# cube.net
KiCad netlist of a schematic drawn in EAGLE
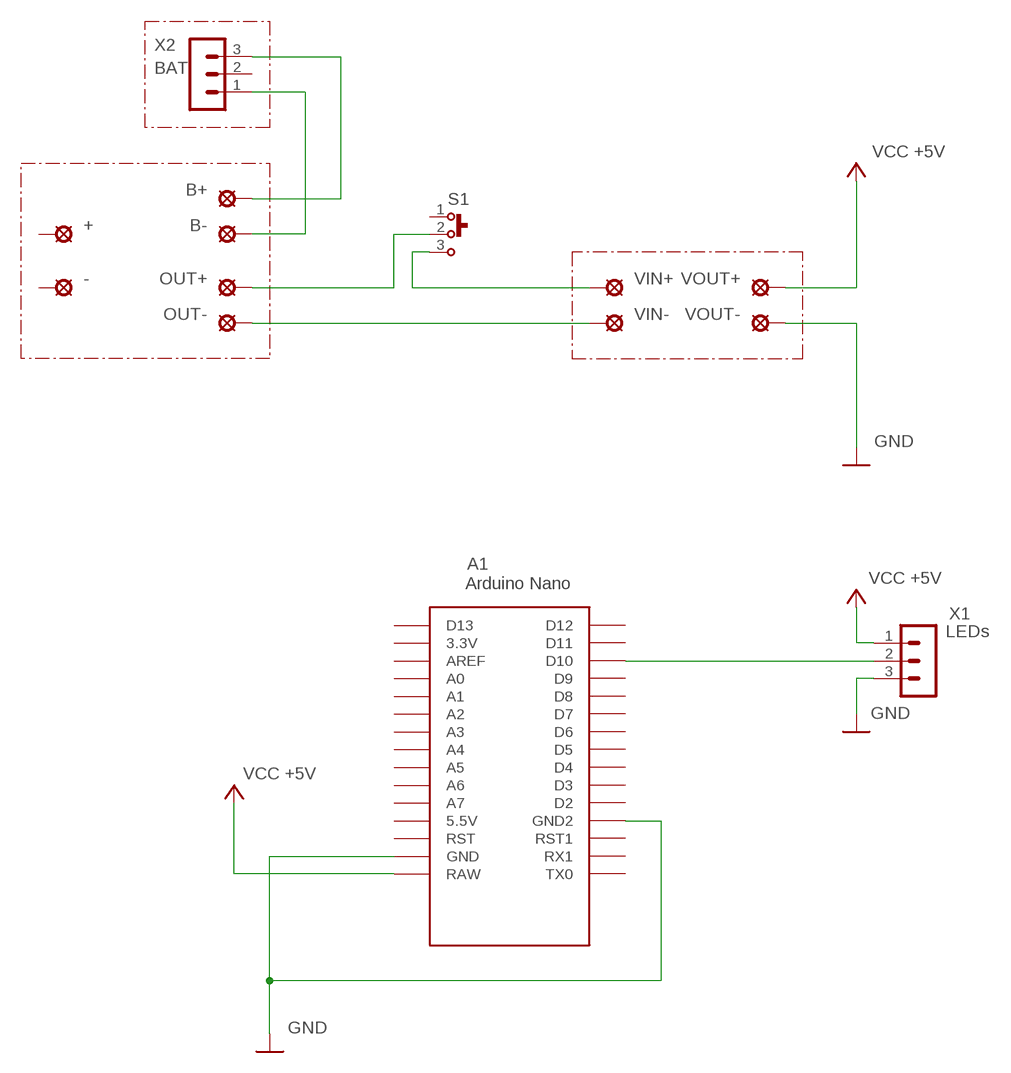
[diagram p0: schematic, sheet 1]

(export (version "E")
  (design (tool "Eeschema 10.0.6"))
  (components
    (comp (ref "+")
      (value "MCS08")
      (footprint "eagle-import:MCS08")
      (libsource (lib "eagle-import") (part "MCS08"))
    )
    (comp (ref "-")
      (value "MCS08")
      (footprint "eagle-import:MCS08")
      (libsource (lib "eagle-import") (part "MCS08"))
    )
    (comp (ref "A1")
      (value "NANO")
      (footprint "eagle-import:NANO")
      (libsource (lib "eagle-import") (part "NANO"))
    )
    (comp (ref "B+")
      (value "MCS08")
      (footprint "eagle-import:MCS08")
      (libsource (lib "eagle-import") (part "MCS08"))
    )
    (comp (ref "B-")
      (value "MCS08")
      (footprint "eagle-import:MCS08")
      (libsource (lib "eagle-import") (part "MCS08"))
    )
    (comp (ref "OUT+")
      (value "MCS08")
      (footprint "eagle-import:MCS08")
      (libsource (lib "eagle-import") (part "MCS08"))
    )
    (comp (ref "OUT-")
      (value "MCS08")
      (footprint "eagle-import:MCS08")
      (libsource (lib "eagle-import") (part "MCS08"))
    )
    (comp (ref "S1")
      (value "EG1218")
      (footprint "eagle-import:EG1218")
      (libsource (lib "eagle-import") (part "EG1218"))
    )
    (comp (ref "VIN+")
      (value "MCS08")
      (footprint "eagle-import:MCS08")
      (libsource (lib "eagle-import") (part "MCS08"))
    )
    (comp (ref "VIN-")
      (value "MCS08")
      (footprint "eagle-import:MCS08")
      (libsource (lib "eagle-import") (part "MCS08"))
    )
    (comp (ref "VOUT+")
      (value "MCS08")
      (footprint "eagle-import:MCS08")
      (libsource (lib "eagle-import") (part "MCS08"))
    )
    (comp (ref "VOUT-")
      (value "MCS08")
      (footprint "eagle-import:MCS08")
      (libsource (lib "eagle-import") (part "MCS08"))
    )
    (comp (ref "X1")
      (value "LEDs")
      (footprint "eagle-import:MA03-1")
      (libsource (lib "eagle-import") (part "MA03-1"))
    )
    (comp (ref "X2")
      (value "BAT")
      (footprint "eagle-import:MA03-1")
      (libsource (lib "eagle-import") (part "MA03-1"))
    )
  )
  (nets
    (net (code "1") (name "GND") (class "Default")
      (node (ref "A1") (pin "GND") (pinfunction "GND_GND") (pintype "bidirectional"))
      (node (ref "A1") (pin "GND1") (pinfunction "GND2_GND1") (pintype "bidirectional"))
      (node (ref "VOUT-") (pin "MP") (pinfunction "MP_MP") (pintype "passive"))
      (node (ref "X1") (pin "3") (pinfunction "3_3") (pintype "passive"))
    )
    (net (code "2") (name "Net-(A1-PadD10)") (class "Default")
      (node (ref "A1") (pin "D10") (pinfunction "D10_D10") (pintype "bidirectional"))
      (node (ref "X1") (pin "2") (pinfunction "2_2") (pintype "passive"))
    )
    (net (code "3") (name "Net-(B+-PadMP)") (class "Default")
      (node (ref "B+") (pin "MP") (pinfunction "MP_MP") (pintype "passive"))
      (node (ref "X2") (pin "3") (pinfunction "3_3") (pintype "passive"))
    )
    (net (code "4") (name "Net-(B--PadMP)") (class "Default")
      (node (ref "B-") (pin "MP") (pinfunction "MP_MP") (pintype "passive"))
      (node (ref "X2") (pin "1") (pinfunction "1_1") (pintype "passive"))
    )
    (net (code "5") (name "Net-(OUT+-PadMP)") (class "Default")
      (node (ref "OUT+") (pin "MP") (pinfunction "MP_MP") (pintype "passive"))
      (node (ref "S1") (pin "2") (pinfunction "2_2") (pintype "passive"))
    )
    (net (code "6") (name "Net-(OUT--PadMP)") (class "Default")
      (node (ref "OUT-") (pin "MP") (pinfunction "MP_MP") (pintype "passive"))
      (node (ref "VIN-") (pin "MP") (pinfunction "MP_MP") (pintype "passive"))
    )
    (net (code "7") (name "Net-(S1-Pad3)") (class "Default")
      (node (ref "S1") (pin "3") (pinfunction "3_3") (pintype "passive"))
      (node (ref "VIN+") (pin "MP") (pinfunction "MP_MP") (pintype "passive"))
    )
    (net (code "8") (name "VCC +5V") (class "Default")
      (node (ref "A1") (pin "RAW") (pinfunction "RAW_RAW") (pintype "bidirectional"))
      (node (ref "VOUT+") (pin "MP") (pinfunction "MP_MP") (pintype "passive"))
      (node (ref "X1") (pin "1") (pinfunction "1_1") (pintype "passive"))
    )
    (net (code "9") (name "unconnected-(+-PadMP)") (class "Default")
      (node (ref "+") (pin "MP") (pinfunction "MP_MP") (pintype "passive"))
    )
    (net (code "10") (name "unconnected-(--PadMP)") (class "Default")
      (node (ref "-") (pin "MP") (pinfunction "MP_MP") (pintype "passive"))
    )
    (net (code "11") (name "unconnected-(A1-5.5V-Pad5V)") (class "Default")
      (node (ref "A1") (pin "5V") (pinfunction "5.5V_5V") (pintype "bidirectional"))
    )
    (net (code "12") (name "unconnected-(A1-Pad3.3V)") (class "Default")
      (node (ref "A1") (pin "3.3V") (pinfunction "3.3V_3.3V") (pintype "bidirectional"))
    )
    (net (code "13") (name "unconnected-(A1-PadA0)") (class "Default")
      (node (ref "A1") (pin "A0") (pinfunction "A0_A0") (pintype "bidirectional"))
    )
    (net (code "14") (name "unconnected-(A1-PadA1)") (class "Default")
      (node (ref "A1") (pin "A1") (pinfunction "A1_A1") (pintype "bidirectional"))
    )
    (net (code "15") (name "unconnected-(A1-PadA2)") (class "Default")
      (node (ref "A1") (pin "A2") (pinfunction "A2_A2") (pintype "bidirectional"))
    )
    (net (code "16") (name "unconnected-(A1-PadA3)") (class "Default")
      (node (ref "A1") (pin "A3") (pinfunction "A3_A3") (pintype "bidirectional"))
    )
    (net (code "17") (name "unconnected-(A1-PadA4)") (class "Default")
      (node (ref "A1") (pin "A4") (pinfunction "A4_A4") (pintype "bidirectional"))
    )
    (net (code "18") (name "unconnected-(A1-PadA5)") (class "Default")
      (node (ref "A1") (pin "A5") (pinfunction "A5_A5") (pintype "bidirectional"))
    )
    (net (code "19") (name "unconnected-(A1-PadA6)") (class "Default")
      (node (ref "A1") (pin "A6") (pinfunction "A6_A6") (pintype "bidirectional"))
    )
    (net (code "20") (name "unconnected-(A1-PadA7)") (class "Default")
      (node (ref "A1") (pin "A7") (pinfunction "A7_A7") (pintype "bidirectional"))
    )
    (net (code "21") (name "unconnected-(A1-PadAREF)") (class "Default")
      (node (ref "A1") (pin "AREF") (pinfunction "AREF_AREF") (pintype "bidirectional"))
    )
    (net (code "22") (name "unconnected-(A1-PadD2)") (class "Default")
      (node (ref "A1") (pin "D2") (pinfunction "D2_D2") (pintype "bidirectional"))
    )
    (net (code "23") (name "unconnected-(A1-PadD3)") (class "Default")
      (node (ref "A1") (pin "D3") (pinfunction "D3_D3") (pintype "bidirectional"))
    )
    (net (code "24") (name "unconnected-(A1-PadD4)") (class "Default")
      (node (ref "A1") (pin "D4") (pinfunction "D4_D4") (pintype "bidirectional"))
    )
    (net (code "25") (name "unconnected-(A1-PadD5)") (class "Default")
      (node (ref "A1") (pin "D5") (pinfunction "D5_D5") (pintype "bidirectional"))
    )
    (net (code "26") (name "unconnected-(A1-PadD6)") (class "Default")
      (node (ref "A1") (pin "D6") (pinfunction "D6_D6") (pintype "bidirectional"))
    )
    (net (code "27") (name "unconnected-(A1-PadD7)") (class "Default")
      (node (ref "A1") (pin "D7") (pinfunction "D7_D7") (pintype "bidirectional"))
    )
    (net (code "28") (name "unconnected-(A1-PadD8)") (class "Default")
      (node (ref "A1") (pin "D8") (pinfunction "D8_D8") (pintype "bidirectional"))
    )
    (net (code "29") (name "unconnected-(A1-PadD9)") (class "Default")
      (node (ref "A1") (pin "D9") (pinfunction "D9_D9") (pintype "bidirectional"))
    )
    (net (code "30") (name "unconnected-(A1-PadD11)") (class "Default")
      (node (ref "A1") (pin "D11") (pinfunction "D11_D11") (pintype "bidirectional"))
    )
    (net (code "31") (name "unconnected-(A1-PadD12)") (class "Default")
      (node (ref "A1") (pin "D12") (pinfunction "D12_D12") (pintype "bidirectional"))
    )
    (net (code "32") (name "unconnected-(A1-PadD13)") (class "Default")
      (node (ref "A1") (pin "D13") (pinfunction "D13_D13") (pintype "bidirectional"))
    )
    (net (code "33") (name "unconnected-(A1-PadRST)") (class "Default")
      (node (ref "A1") (pin "RST") (pinfunction "RST_RST") (pintype "bidirectional"))
    )
    (net (code "34") (name "unconnected-(A1-PadRST1)") (class "Default")
      (node (ref "A1") (pin "RST1") (pinfunction "RST1_RST1") (pintype "bidirectional"))
    )
    (net (code "35") (name "unconnected-(A1-PadRX1)") (class "Default")
      (node (ref "A1") (pin "RX1") (pinfunction "RX1_RX1") (pintype "bidirectional"))
    )
    (net (code "36") (name "unconnected-(A1-PadTX0)") (class "Default")
      (node (ref "A1") (pin "TX0") (pinfunction "TX0_TX0") (pintype "bidirectional"))
    )
    (net (code "37") (name "unconnected-(S1-Pad1)") (class "Default")
      (node (ref "S1") (pin "1") (pinfunction "1_1") (pintype "passive"))
    )
    (net (code "38") (name "unconnected-(X2-Pad2)") (class "Default")
      (node (ref "X2") (pin "2") (pinfunction "2_2") (pintype "passive"))
    )
  )
)
